# hp1.net
KiCad netlist of a schematic drawn in EAGLE
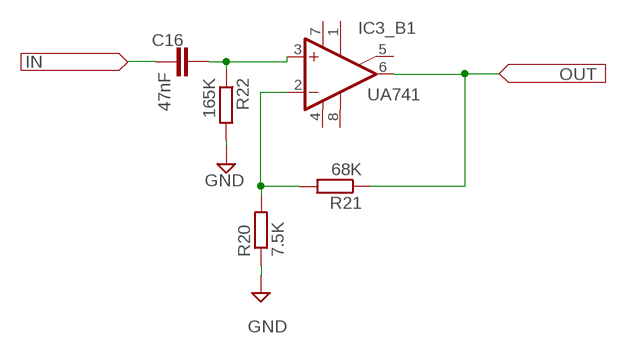
[diagram p0: schematic, sheet 1]

(export (version "E")
  (design (tool "Eeschema 10.0.6"))
  (components
    (comp (ref "C16")
      (value "47nF")
      (footprint "eagle-import:C025-025X050")
      (libsource (lib "eagle-import") (part "C-EU025-025X050"))
    )
    (comp (ref "IC3_B1")
      (value "LF356N")
      (footprint "eagle-import:DIL08")
      (libsource (lib "eagle-import") (part "LF356N"))
    )
    (comp (ref "R20")
      (value "7.5K")
      (footprint "eagle-import:0207_10")
      (libsource (lib "eagle-import") (part "R-EU_0207/10"))
    )
    (comp (ref "R21")
      (value "68K")
      (footprint "eagle-import:0207_10")
      (libsource (lib "eagle-import") (part "R-EU_0207/10"))
    )
    (comp (ref "R22")
      (value "165K")
      (footprint "eagle-import:0207_10")
      (libsource (lib "eagle-import") (part "R-EU_0207/10"))
    )
  )
  (nets
    (net (code "1") (name "/V+") (class "Default")
      (node (ref "IC3_B1") (pin "7") (pinfunction "V+_7") (pintype "power_in"))
    )
    (net (code "2") (name "/V-") (class "Default")
      (node (ref "IC3_B1") (pin "4") (pinfunction "V-_4") (pintype "power_in"))
    )
    (net (code "3") (name "GND") (class "Default")
      (node (ref "R20") (pin "1") (pinfunction "1_1") (pintype "passive"))
      (node (ref "R22") (pin "2") (pinfunction "2_2") (pintype "passive"))
    )
    (net (code "4") (name "Net-(C16-Pad1)") (class "Default")
      (node (ref "C16") (pin "1") (pinfunction "1_1") (pintype "passive"))
      (node (ref "R22") (pin "1") (pinfunction "1_1") (pintype "passive"))
    )
    (net (code "5") (name "Net-(IC3_B1-OUT)") (class "Default")
      (node (ref "IC3_B1") (pin "6") (pinfunction "OUT_6") (pintype "output"))
      (node (ref "R21") (pin "1") (pinfunction "1_1") (pintype "passive"))
    )
    (net (code "6") (name "Net-(R20-Pad2)") (class "Default")
      (node (ref "R20") (pin "2") (pinfunction "2_2") (pintype "passive"))
      (node (ref "R21") (pin "2") (pinfunction "2_2") (pintype "passive"))
    )
    (net (code "7") (name "unconnected-(C16-Pad2)") (class "Default")
      (node (ref "C16") (pin "2") (pinfunction "2_2") (pintype "passive"))
    )
    (net (code "8") (name "unconnected-(IC3_B1-+IN-Pad3)") (class "Default")
      (node (ref "IC3_B1") (pin "3") (pinfunction "+IN_3") (pintype "input"))
    )
    (net (code "9") (name "unconnected-(IC3_B1--IN-Pad2)") (class "Default")
      (node (ref "IC3_B1") (pin "2") (pinfunction "-IN_2") (pintype "input"))
    )
    (net (code "10") (name "unconnected-(IC3_B1-ON1-Pad1)") (class "Default")
      (node (ref "IC3_B1") (pin "1") (pinfunction "ON1_1") (pintype "passive"))
    )
    (net (code "11") (name "unconnected-(IC3_B1-ON2-Pad5)") (class "Default")
      (node (ref "IC3_B1") (pin "5") (pinfunction "ON2_5") (pintype "passive"))
    )
    (net (code "12") (name "unconnected-(IC3_B1-OPT-Pad8)") (class "Default")
      (node (ref "IC3_B1") (pin "8") (pinfunction "OPT_8") (pintype "passive"))
    )
  )
)
